# ADC-Filter.net
KiCad netlist of a schematic drawn in Altium Designer
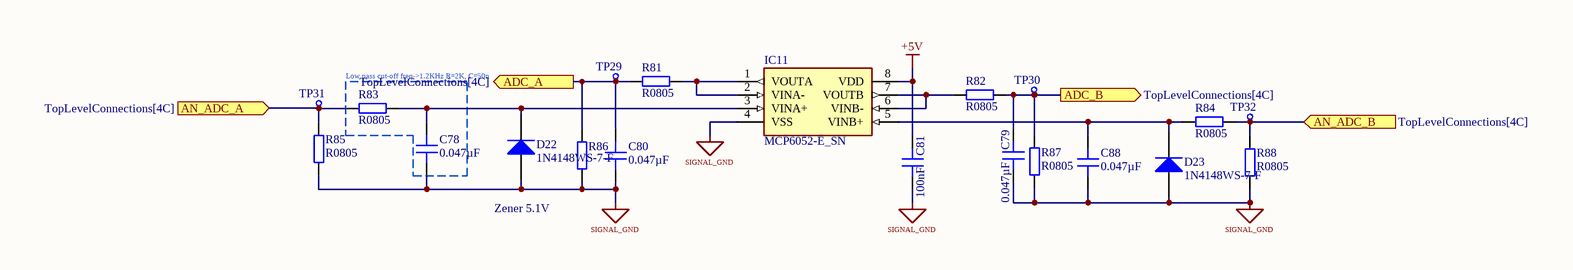
[diagram p0: ADC-Filter.SchDoc]

(export (version "E")
  (design (tool "Eeschema 10.0.6"))
  (components
    (comp (ref "C78")
      (value "0.047µF")
      (footprint "CAP 0805_2012")
      (description "CAP CER 0.047UF 50V X8R 0805")
      (fields (field (name "PART NUMBER") "08055F473K4T2A") (field (name "MANUFACTURER") "AVX Corporation"))
      (libsource (lib "Celestial Altium Library FIREWALL") (part "Capacitor"))
    )
    (comp (ref "C79")
      (value "0.047µF")
      (footprint "CAP 0805_2012")
      (description "CAP CER 0.047UF 50V X8R 0805")
      (fields (field (name "PART NUMBER") "08055F473K4T2A") (field (name "MANUFACTURER") "AVX Corporation"))
      (libsource (lib "Celestial Altium Library FIREWALL") (part "Capacitor"))
    )
    (comp (ref "C80")
      (value "0.047µF")
      (footprint "CAP 0805_2012")
      (description "CAP CER 0.047UF 50V X8R 0805")
      (fields (field (name "PART NUMBER") "08055F473K4T2A") (field (name "MANUFACTURER") "AVX Corporation"))
      (libsource (lib "Celestial Altium Library FIREWALL") (part "Capacitor"))
    )
    (comp (ref "C81")
      (value "100nF")
      (footprint "CAP 0805_2012")
      (description "CAP CER 10UF 10V X7R 0805")
      (fields
        (field (name "PART NUMBER") "C2012X7R1A106K125AE")
        (field (name "MANUFACTURER") "TDK Corporation")
      )
      (libsource (lib "Celestial Altium Library FIREWALL") (part "Capacitor"))
    )
    (comp (ref "C88")
      (value "0.047µF")
      (footprint "CAP 0805_2012")
      (description "CAP CER 0.047UF 50V X8R 0805")
      (fields (field (name "PART NUMBER") "08055F473K4T2A") (field (name "MANUFACTURER") "AVX Corporation"))
      (libsource (lib "Celestial Altium Library FIREWALL") (part "Capacitor"))
    )
    (comp (ref "D22")
      (value "1N4148WS-7-F")
      (footprint "DIOD-SOD323-2-A_V")
      (description "Fast Switching Diode, 75 V, 0.3 A, -65 to 150 degC, 2-Pin SOD323, RoHS, Tape and Reel")
      (fields (field (name "MANUFACTURER") "Diodes Inc"))
      (libsource (lib "LART") (part "D-AK-2"))
    )
    (comp (ref "D23")
      (value "1N4148WS-7-F")
      (footprint "DIOD-SOD323-2-A_V")
      (description "Fast Switching Diode, 75 V, 0.3 A, -65 to 150 degC, 2-Pin SOD323, RoHS, Tape and Reel")
      (fields (field (name "MANUFACTURER") "Diodes Inc"))
      (libsource (lib "LART") (part "D-AK-2"))
    )
    (comp (ref "IC11")
      (value "MCP6052-E_SN")
      (footprint "SOIC127P600X175-8N")
      (description "Integrated Circuit")
      (fields
        (field (name "MANUFACTURER_PART_NUMBER") "MCP6052-E/SN")
        (field (name "MOUSER PART NUMBER") "579-MCP6052-E/SN")
      )
      (libsource (lib "DesagoSch") (part "MCP6052-E_SN"))
    )
    (comp (ref "R81")
      (value "R0805")
      (footprint "RES_0805")
      (description "Resistor SMD 0805")
      (libsource (lib "Pedro_sch_lib") (part "RES_0805"))
    )
    (comp (ref "R82")
      (value "R0805")
      (footprint "RES_0805")
      (description "Resistor SMD 0805")
      (libsource (lib "Pedro_sch_lib") (part "RES_0805"))
    )
    (comp (ref "R83")
      (value "R0805")
      (footprint "RES_0805")
      (description "Resistor SMD 0805")
      (libsource (lib "Pedro_sch_lib") (part "RES_0805"))
    )
    (comp (ref "R84")
      (value "R0805")
      (footprint "RES_0805")
      (description "Resistor SMD 0805")
      (libsource (lib "Pedro_sch_lib") (part "RES_0805"))
    )
    (comp (ref "R85")
      (value "R0805")
      (footprint "RES_0805")
      (description "Resistor SMD 0805")
      (libsource (lib "Pedro_sch_lib") (part "RES_0805"))
    )
    (comp (ref "R86")
      (value "R0805")
      (footprint "RES_0805")
      (description "Resistor SMD 0805")
      (libsource (lib "Pedro_sch_lib") (part "RES_0805"))
    )
    (comp (ref "R87")
      (value "R0805")
      (footprint "RES_0805")
      (description "Resistor SMD 0805")
      (libsource (lib "Pedro_sch_lib") (part "RES_0805"))
    )
    (comp (ref "R88")
      (value "R0805")
      (footprint "RES_0805")
      (description "Resistor SMD 0805")
      (libsource (lib "Pedro_sch_lib") (part "RES_0805"))
    )
    (comp (ref "TP29")
      (value "TestPad")
      (footprint "Test Pad Small")
      (libsource (lib "ImegurasLib") (part "TestPad"))
    )
    (comp (ref "TP30")
      (value "TestPad")
      (footprint "Test Pad Small")
      (libsource (lib "ImegurasLib") (part "TestPad"))
    )
    (comp (ref "TP31")
      (value "TestPad")
      (footprint "Test Pad Small")
      (libsource (lib "ImegurasLib") (part "TestPad"))
    )
    (comp (ref "TP32")
      (value "TestPad")
      (footprint "Test Pad Small")
      (libsource (lib "ImegurasLib") (part "TestPad"))
    )
  )
  (nets
    (net (code "1") (name "+5V") (class "Default")
      (node (ref "C81") (pin "2") (pinfunction "2_2") (pintype "passive"))
      (node (ref "IC11") (pin "8") (pinfunction "VDD_8") (pintype "power_in"))
    )
    (net (code "3") (name "/ADC_A") (class "Default")
      (node (ref "C80") (pin "2") (pinfunction "2_2") (pintype "passive"))
      (node (ref "R81") (pin "2") (pinfunction "2_2") (pintype "passive"))
      (node (ref "R86") (pin "2") (pinfunction "2_2") (pintype "passive"))
      (node (ref "TP29") (pin "P2") (pinfunction "P2_P2") (pintype "passive"))
    )
    (net (code "4") (name "/ADC_B") (class "Default")
      (node (ref "C79") (pin "2") (pinfunction "2_2") (pintype "passive"))
      (node (ref "R82") (pin "1") (pinfunction "1_1") (pintype "passive"))
      (node (ref "R87") (pin "1") (pinfunction "1_1") (pintype "passive"))
      (node (ref "TP30") (pin "P2") (pinfunction "P2_P2") (pintype "passive"))
    )
    (net (code "5") (name "/AN_ADC_A") (class "Default")
      (node (ref "R83") (pin "1") (pinfunction "1_1") (pintype "passive"))
      (node (ref "R85") (pin "2") (pinfunction "2_2") (pintype "passive"))
      (node (ref "TP31") (pin "P2") (pinfunction "P2_P2") (pintype "passive"))
    )
    (net (code "6") (name "/AN_ADC_B") (class "Default")
      (node (ref "R84") (pin "2") (pinfunction "2_2") (pintype "passive"))
      (node (ref "R88") (pin "2") (pinfunction "2_2") (pintype "passive"))
      (node (ref "TP32") (pin "P2") (pinfunction "P2_P2") (pintype "passive"))
    )
    (net (code "7") (name "Net-(D22-K)") (class "Default")
      (node (ref "C78") (pin "2") (pinfunction "2_2") (pintype "passive"))
      (node (ref "D22") (pin "2") (pinfunction "K_2") (pintype "passive"))
      (node (ref "IC11") (pin "3") (pinfunction "VINA+_3") (pintype "input"))
      (node (ref "R83") (pin "2") (pinfunction "2_2") (pintype "passive"))
    )
    (net (code "8") (name "Net-(D23-K)") (class "Default")
      (node (ref "C88") (pin "2") (pinfunction "2_2") (pintype "passive"))
      (node (ref "D23") (pin "2") (pinfunction "K_2") (pintype "passive"))
      (node (ref "IC11") (pin "5") (pinfunction "VINB+_5") (pintype "input"))
      (node (ref "R84") (pin "1") (pinfunction "1_1") (pintype "passive"))
    )
    (net (code "9") (name "Net-(IC11-VINA-)") (class "Default")
      (node (ref "IC11") (pin "1") (pinfunction "VOUTA_1") (pintype "output"))
      (node (ref "IC11") (pin "2") (pinfunction "VINA-_2") (pintype "input"))
      (node (ref "R81") (pin "1") (pinfunction "1_1") (pintype "passive"))
    )
    (net (code "10") (name "Net-(IC11-VINB-)") (class "Default")
      (node (ref "IC11") (pin "6") (pinfunction "VINB-_6") (pintype "input"))
      (node (ref "IC11") (pin "7") (pinfunction "VOUTB_7") (pintype "output"))
      (node (ref "R82") (pin "2") (pinfunction "2_2") (pintype "passive"))
    )
    (net (code "11") (name "SIGNAL_GND") (class "Default")
      (node (ref "C78") (pin "1") (pinfunction "1_1") (pintype "passive"))
      (node (ref "C79") (pin "1") (pinfunction "1_1") (pintype "passive"))
      (node (ref "C80") (pin "1") (pinfunction "1_1") (pintype "passive"))
      (node (ref "C81") (pin "1") (pinfunction "1_1") (pintype "passive"))
      (node (ref "C88") (pin "1") (pinfunction "1_1") (pintype "passive"))
      (node (ref "D22") (pin "1") (pinfunction "A_1") (pintype "passive"))
      (node (ref "D23") (pin "1") (pinfunction "A_1") (pintype "passive"))
      (node (ref "IC11") (pin "4") (pinfunction "VSS_4") (pintype "power_in"))
      (node (ref "R85") (pin "1") (pinfunction "1_1") (pintype "passive"))
      (node (ref "R86") (pin "1") (pinfunction "1_1") (pintype "passive"))
      (node (ref "R87") (pin "2") (pinfunction "2_2") (pintype "passive"))
      (node (ref "R88") (pin "1") (pinfunction "1_1") (pintype "passive"))
    )
  )
)
